# LED_Matrix-2.net
KiCad netlist of a schematic drawn in Altium Designer
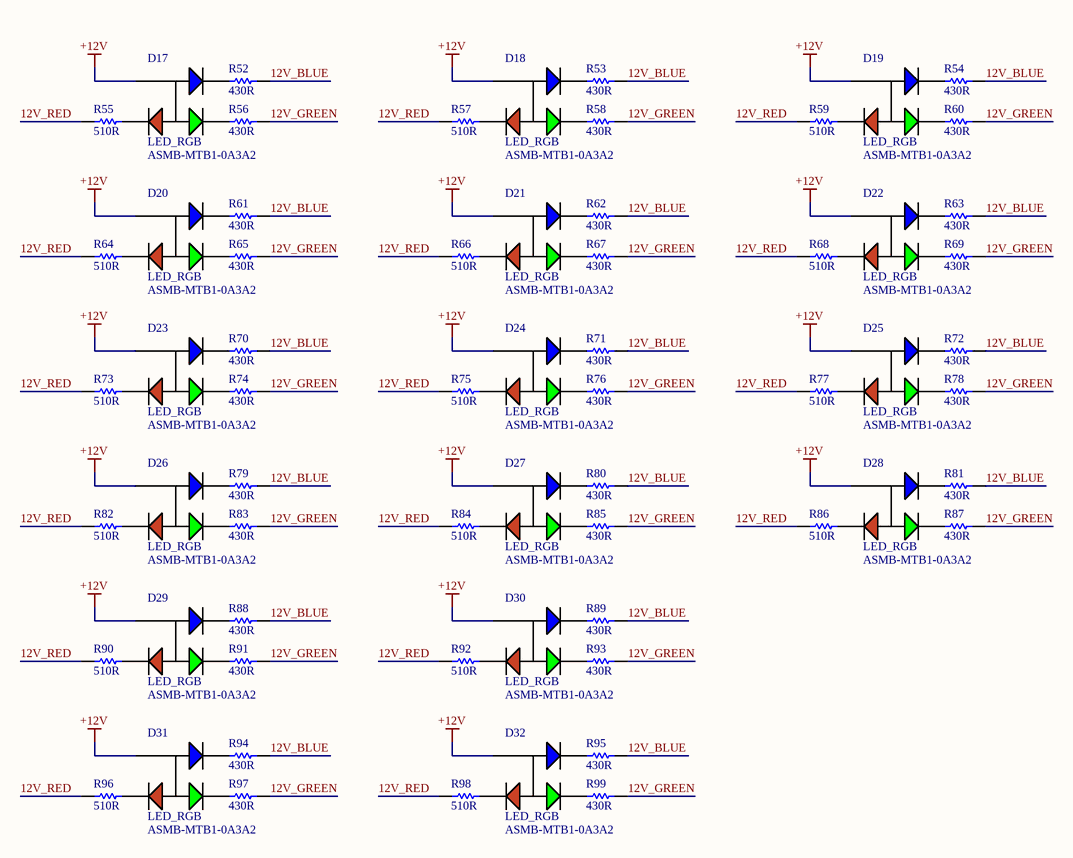
[diagram p0: LED Matrix-2.SchDoc]

(export (version "E")
  (design (tool "Eeschema 10.0.6"))
  (components
    (comp (ref "D17")
      (value "LED_RGB")
      (footprint "LED_RGB")
      (description "LED RGB DIFFUSED 4PLCC SMD")
      (fields (field (name "MANUFACTURER PART NUMBER 1") "ASMB-MTB1-0A3A2"))
      (libsource (lib "UWRT_Schematic_Library_2020") (part "LED_RGB"))
    )
    (comp (ref "D18")
      (value "LED_RGB")
      (footprint "LED_RGB")
      (description "LED RGB DIFFUSED 4PLCC SMD")
      (fields (field (name "MANUFACTURER PART NUMBER 1") "ASMB-MTB1-0A3A2"))
      (libsource (lib "UWRT_Schematic_Library_2020") (part "LED_RGB"))
    )
    (comp (ref "D19")
      (value "LED_RGB")
      (footprint "LED_RGB")
      (description "LED RGB DIFFUSED 4PLCC SMD")
      (fields (field (name "MANUFACTURER PART NUMBER 1") "ASMB-MTB1-0A3A2"))
      (libsource (lib "UWRT_Schematic_Library_2020") (part "LED_RGB"))
    )
    (comp (ref "D20")
      (value "LED_RGB")
      (footprint "LED_RGB")
      (description "LED RGB DIFFUSED 4PLCC SMD")
      (fields (field (name "MANUFACTURER PART NUMBER 1") "ASMB-MTB1-0A3A2"))
      (libsource (lib "UWRT_Schematic_Library_2020") (part "LED_RGB"))
    )
    (comp (ref "D21")
      (value "LED_RGB")
      (footprint "LED_RGB")
      (description "LED RGB DIFFUSED 4PLCC SMD")
      (fields (field (name "MANUFACTURER PART NUMBER 1") "ASMB-MTB1-0A3A2"))
      (libsource (lib "UWRT_Schematic_Library_2020") (part "LED_RGB"))
    )
    (comp (ref "D22")
      (value "LED_RGB")
      (footprint "LED_RGB")
      (description "LED RGB DIFFUSED 4PLCC SMD")
      (fields (field (name "MANUFACTURER PART NUMBER 1") "ASMB-MTB1-0A3A2"))
      (libsource (lib "UWRT_Schematic_Library_2020") (part "LED_RGB"))
    )
    (comp (ref "D23")
      (value "LED_RGB")
      (footprint "LED_RGB")
      (description "LED RGB DIFFUSED 4PLCC SMD")
      (fields (field (name "MANUFACTURER PART NUMBER 1") "ASMB-MTB1-0A3A2"))
      (libsource (lib "UWRT_Schematic_Library_2020") (part "LED_RGB"))
    )
    (comp (ref "D24")
      (value "LED_RGB")
      (footprint "LED_RGB")
      (description "LED RGB DIFFUSED 4PLCC SMD")
      (fields (field (name "MANUFACTURER PART NUMBER 1") "ASMB-MTB1-0A3A2"))
      (libsource (lib "UWRT_Schematic_Library_2020") (part "LED_RGB"))
    )
    (comp (ref "D25")
      (value "LED_RGB")
      (footprint "LED_RGB")
      (description "LED RGB DIFFUSED 4PLCC SMD")
      (fields (field (name "MANUFACTURER PART NUMBER 1") "ASMB-MTB1-0A3A2"))
      (libsource (lib "UWRT_Schematic_Library_2020") (part "LED_RGB"))
    )
    (comp (ref "D26")
      (value "LED_RGB")
      (footprint "LED_RGB")
      (description "LED RGB DIFFUSED 4PLCC SMD")
      (fields (field (name "MANUFACTURER PART NUMBER 1") "ASMB-MTB1-0A3A2"))
      (libsource (lib "UWRT_Schematic_Library_2020") (part "LED_RGB"))
    )
    (comp (ref "D27")
      (value "LED_RGB")
      (footprint "LED_RGB")
      (description "LED RGB DIFFUSED 4PLCC SMD")
      (fields (field (name "MANUFACTURER PART NUMBER 1") "ASMB-MTB1-0A3A2"))
      (libsource (lib "UWRT_Schematic_Library_2020") (part "LED_RGB"))
    )
    (comp (ref "D28")
      (value "LED_RGB")
      (footprint "LED_RGB")
      (description "LED RGB DIFFUSED 4PLCC SMD")
      (fields (field (name "MANUFACTURER PART NUMBER 1") "ASMB-MTB1-0A3A2"))
      (libsource (lib "UWRT_Schematic_Library_2020") (part "LED_RGB"))
    )
    (comp (ref "D29")
      (value "LED_RGB")
      (footprint "LED_RGB")
      (description "LED RGB DIFFUSED 4PLCC SMD")
      (fields (field (name "MANUFACTURER PART NUMBER 1") "ASMB-MTB1-0A3A2"))
      (libsource (lib "UWRT_Schematic_Library_2020") (part "LED_RGB"))
    )
    (comp (ref "D30")
      (value "LED_RGB")
      (footprint "LED_RGB")
      (description "LED RGB DIFFUSED 4PLCC SMD")
      (fields (field (name "MANUFACTURER PART NUMBER 1") "ASMB-MTB1-0A3A2"))
      (libsource (lib "UWRT_Schematic_Library_2020") (part "LED_RGB"))
    )
    (comp (ref "D31")
      (value "LED_RGB")
      (footprint "LED_RGB")
      (description "LED RGB DIFFUSED 4PLCC SMD")
      (fields (field (name "MANUFACTURER PART NUMBER 1") "ASMB-MTB1-0A3A2"))
      (libsource (lib "UWRT_Schematic_Library_2020") (part "LED_RGB"))
    )
    (comp (ref "D32")
      (value "LED_RGB")
      (footprint "LED_RGB")
      (description "LED RGB DIFFUSED 4PLCC SMD")
      (fields (field (name "MANUFACTURER PART NUMBER 1") "ASMB-MTB1-0A3A2"))
      (libsource (lib "UWRT_Schematic_Library_2020") (part "LED_RGB"))
    )
    (comp (ref "R52")
      (value "430R")
      (footprint "RESC2012X60N")
      (description "RES SMD 430 OHM 1% 1/8W 0805")
      (fields (field (name "TOLERANCE") "1%") (field (name "Comment") "RES_430R_0805"))
      (libsource (lib "UWRT_Schematic_Library_2020") (part "RES_430R_0805"))
    )
    (comp (ref "R53")
      (value "430R")
      (footprint "RESC2012X60N")
      (description "RES SMD 430 OHM 1% 1/8W 0805")
      (fields (field (name "TOLERANCE") "1%") (field (name "Comment") "RES_430R_0805"))
      (libsource (lib "UWRT_Schematic_Library_2020") (part "RES_430R_0805"))
    )
    (comp (ref "R54")
      (value "430R")
      (footprint "RESC2012X60N")
      (description "RES SMD 430 OHM 1% 1/8W 0805")
      (fields (field (name "TOLERANCE") "1%") (field (name "Comment") "RES_430R_0805"))
      (libsource (lib "UWRT_Schematic_Library_2020") (part "RES_430R_0805"))
    )
    (comp (ref "R55")
      (value "510R")
      (footprint "RESC2012X60N")
      (description "RES SMD 510 OHM 1% 1/8W 0805")
      (fields (field (name "TOLERANCE") "1%") (field (name "Comment") "RES_510R_0805"))
      (libsource (lib "UWRT_Schematic_Library_2020") (part "RES_510R_0805"))
    )
    (comp (ref "R56")
      (value "430R")
      (footprint "RESC2012X60N")
      (description "RES SMD 430 OHM 1% 1/8W 0805")
      (fields (field (name "TOLERANCE") "1%") (field (name "Comment") "RES_430R_0805"))
      (libsource (lib "UWRT_Schematic_Library_2020") (part "RES_430R_0805"))
    )
    (comp (ref "R57")
      (value "510R")
      (footprint "RESC2012X60N")
      (description "RES SMD 510 OHM 1% 1/8W 0805")
      (fields (field (name "TOLERANCE") "1%") (field (name "Comment") "RES_510R_0805"))
      (libsource (lib "UWRT_Schematic_Library_2020") (part "RES_510R_0805"))
    )
    (comp (ref "R58")
      (value "430R")
      (footprint "RESC2012X60N")
      (description "RES SMD 430 OHM 1% 1/8W 0805")
      (fields (field (name "TOLERANCE") "1%") (field (name "Comment") "RES_430R_0805"))
      (libsource (lib "UWRT_Schematic_Library_2020") (part "RES_430R_0805"))
    )
    (comp (ref "R59")
      (value "510R")
      (footprint "RESC2012X60N")
      (description "RES SMD 510 OHM 1% 1/8W 0805")
      (fields (field (name "TOLERANCE") "1%") (field (name "Comment") "RES_510R_0805"))
      (libsource (lib "UWRT_Schematic_Library_2020") (part "RES_510R_0805"))
    )
    (comp (ref "R60")
      (value "430R")
      (footprint "RESC2012X60N")
      (description "RES SMD 430 OHM 1% 1/8W 0805")
      (fields (field (name "TOLERANCE") "1%") (field (name "Comment") "RES_430R_0805"))
      (libsource (lib "UWRT_Schematic_Library_2020") (part "RES_430R_0805"))
    )
    (comp (ref "R61")
      (value "430R")
      (footprint "RESC2012X60N")
      (description "RES SMD 430 OHM 1% 1/8W 0805")
      (fields (field (name "TOLERANCE") "1%") (field (name "Comment") "RES_430R_0805"))
      (libsource (lib "UWRT_Schematic_Library_2020") (part "RES_430R_0805"))
    )
    (comp (ref "R62")
      (value "430R")
      (footprint "RESC2012X60N")
      (description "RES SMD 430 OHM 1% 1/8W 0805")
      (fields (field (name "TOLERANCE") "1%") (field (name "Comment") "RES_430R_0805"))
      (libsource (lib "UWRT_Schematic_Library_2020") (part "RES_430R_0805"))
    )
    (comp (ref "R63")
      (value "430R")
      (footprint "RESC2012X60N")
      (description "RES SMD 430 OHM 1% 1/8W 0805")
      (fields (field (name "TOLERANCE") "1%") (field (name "Comment") "RES_430R_0805"))
      (libsource (lib "UWRT_Schematic_Library_2020") (part "RES_430R_0805"))
    )
    (comp (ref "R64")
      (value "510R")
      (footprint "RESC2012X60N")
      (description "RES SMD 510 OHM 1% 1/8W 0805")
      (fields (field (name "TOLERANCE") "1%") (field (name "Comment") "RES_510R_0805"))
      (libsource (lib "UWRT_Schematic_Library_2020") (part "RES_510R_0805"))
    )
    (comp (ref "R65")
      (value "430R")
      (footprint "RESC2012X60N")
      (description "RES SMD 430 OHM 1% 1/8W 0805")
      (fields (field (name "TOLERANCE") "1%") (field (name "Comment") "RES_430R_0805"))
      (libsource (lib "UWRT_Schematic_Library_2020") (part "RES_430R_0805"))
    )
    (comp (ref "R66")
      (value "510R")
      (footprint "RESC2012X60N")
      (description "RES SMD 510 OHM 1% 1/8W 0805")
      (fields (field (name "TOLERANCE") "1%") (field (name "Comment") "RES_510R_0805"))
      (libsource (lib "UWRT_Schematic_Library_2020") (part "RES_510R_0805"))
    )
    (comp (ref "R67")
      (value "430R")
      (footprint "RESC2012X60N")
      (description "RES SMD 430 OHM 1% 1/8W 0805")
      (fields (field (name "TOLERANCE") "1%") (field (name "Comment") "RES_430R_0805"))
      (libsource (lib "UWRT_Schematic_Library_2020") (part "RES_430R_0805"))
    )
    (comp (ref "R68")
      (value "510R")
      (footprint "RESC2012X60N")
      (description "RES SMD 510 OHM 1% 1/8W 0805")
      (fields (field (name "TOLERANCE") "1%") (field (name "Comment") "RES_510R_0805"))
      (libsource (lib "UWRT_Schematic_Library_2020") (part "RES_510R_0805"))
    )
    (comp (ref "R69")
      (value "430R")
      (footprint "RESC2012X60N")
      (description "RES SMD 430 OHM 1% 1/8W 0805")
      (fields (field (name "TOLERANCE") "1%") (field (name "Comment") "RES_430R_0805"))
      (libsource (lib "UWRT_Schematic_Library_2020") (part "RES_430R_0805"))
    )
    (comp (ref "R70")
      (value "430R")
      (footprint "RESC2012X60N")
      (description "RES SMD 430 OHM 1% 1/8W 0805")
      (fields (field (name "TOLERANCE") "1%") (field (name "Comment") "RES_430R_0805"))
      (libsource (lib "UWRT_Schematic_Library_2020") (part "RES_430R_0805"))
    )
    (comp (ref "R71")
      (value "430R")
      (footprint "RESC2012X60N")
      (description "RES SMD 430 OHM 1% 1/8W 0805")
      (fields (field (name "TOLERANCE") "1%") (field (name "Comment") "RES_430R_0805"))
      (libsource (lib "UWRT_Schematic_Library_2020") (part "RES_430R_0805"))
    )
    (comp (ref "R72")
      (value "430R")
      (footprint "RESC2012X60N")
      (description "RES SMD 430 OHM 1% 1/8W 0805")
      (fields (field (name "TOLERANCE") "1%") (field (name "Comment") "RES_430R_0805"))
      (libsource (lib "UWRT_Schematic_Library_2020") (part "RES_430R_0805"))
    )
    (comp (ref "R73")
      (value "510R")
      (footprint "RESC2012X60N")
      (description "RES SMD 510 OHM 1% 1/8W 0805")
      (fields (field (name "TOLERANCE") "1%") (field (name "Comment") "RES_510R_0805"))
      (libsource (lib "UWRT_Schematic_Library_2020") (part "RES_510R_0805"))
    )
    (comp (ref "R74")
      (value "430R")
      (footprint "RESC2012X60N")
      (description "RES SMD 430 OHM 1% 1/8W 0805")
      (fields (field (name "TOLERANCE") "1%") (field (name "Comment") "RES_430R_0805"))
      (libsource (lib "UWRT_Schematic_Library_2020") (part "RES_430R_0805"))
    )
    (comp (ref "R75")
      (value "510R")
      (footprint "RESC2012X60N")
      (description "RES SMD 510 OHM 1% 1/8W 0805")
      (fields (field (name "TOLERANCE") "1%") (field (name "Comment") "RES_510R_0805"))
      (libsource (lib "UWRT_Schematic_Library_2020") (part "RES_510R_0805"))
    )
    (comp (ref "R76")
      (value "430R")
      (footprint "RESC2012X60N")
      (description "RES SMD 430 OHM 1% 1/8W 0805")
      (fields (field (name "TOLERANCE") "1%") (field (name "Comment") "RES_430R_0805"))
      (libsource (lib "UWRT_Schematic_Library_2020") (part "RES_430R_0805"))
    )
    (comp (ref "R77")
      (value "510R")
      (footprint "RESC2012X60N")
      (description "RES SMD 510 OHM 1% 1/8W 0805")
      (fields (field (name "TOLERANCE") "1%") (field (name "Comment") "RES_510R_0805"))
      (libsource (lib "UWRT_Schematic_Library_2020") (part "RES_510R_0805"))
    )
    (comp (ref "R78")
      (value "430R")
      (footprint "RESC2012X60N")
      (description "RES SMD 430 OHM 1% 1/8W 0805")
      (fields (field (name "TOLERANCE") "1%") (field (name "Comment") "RES_430R_0805"))
      (libsource (lib "UWRT_Schematic_Library_2020") (part "RES_430R_0805"))
    )
    (comp (ref "R79")
      (value "430R")
      (footprint "RESC2012X60N")
      (description "RES SMD 430 OHM 1% 1/8W 0805")
      (fields (field (name "TOLERANCE") "1%") (field (name "Comment") "RES_430R_0805"))
      (libsource (lib "UWRT_Schematic_Library_2020") (part "RES_430R_0805"))
    )
    (comp (ref "R80")
      (value "430R")
      (footprint "RESC2012X60N")
      (description "RES SMD 430 OHM 1% 1/8W 0805")
      (fields (field (name "TOLERANCE") "1%") (field (name "Comment") "RES_430R_0805"))
      (libsource (lib "UWRT_Schematic_Library_2020") (part "RES_430R_0805"))
    )
    (comp (ref "R81")
      (value "430R")
      (footprint "RESC2012X60N")
      (description "RES SMD 430 OHM 1% 1/8W 0805")
      (fields (field (name "TOLERANCE") "1%") (field (name "Comment") "RES_430R_0805"))
      (libsource (lib "UWRT_Schematic_Library_2020") (part "RES_430R_0805"))
    )
    (comp (ref "R82")
      (value "510R")
      (footprint "RESC2012X60N")
      (description "RES SMD 510 OHM 1% 1/8W 0805")
      (fields (field (name "TOLERANCE") "1%") (field (name "Comment") "RES_510R_0805"))
      (libsource (lib "UWRT_Schematic_Library_2020") (part "RES_510R_0805"))
    )
    (comp (ref "R83")
      (value "430R")
      (footprint "RESC2012X60N")
      (description "RES SMD 430 OHM 1% 1/8W 0805")
      (fields (field (name "TOLERANCE") "1%") (field (name "Comment") "RES_430R_0805"))
      (libsource (lib "UWRT_Schematic_Library_2020") (part "RES_430R_0805"))
    )
    (comp (ref "R84")
      (value "510R")
      (footprint "RESC2012X60N")
      (description "RES SMD 510 OHM 1% 1/8W 0805")
      (fields (field (name "TOLERANCE") "1%") (field (name "Comment") "RES_510R_0805"))
      (libsource (lib "UWRT_Schematic_Library_2020") (part "RES_510R_0805"))
    )
    (comp (ref "R85")
      (value "430R")
      (footprint "RESC2012X60N")
      (description "RES SMD 430 OHM 1% 1/8W 0805")
      (fields (field (name "TOLERANCE") "1%") (field (name "Comment") "RES_430R_0805"))
      (libsource (lib "UWRT_Schematic_Library_2020") (part "RES_430R_0805"))
    )
    (comp (ref "R86")
      (value "510R")
      (footprint "RESC2012X60N")
      (description "RES SMD 510 OHM 1% 1/8W 0805")
      (fields (field (name "TOLERANCE") "1%") (field (name "Comment") "RES_510R_0805"))
      (libsource (lib "UWRT_Schematic_Library_2020") (part "RES_510R_0805"))
    )
    (comp (ref "R87")
      (value "430R")
      (footprint "RESC2012X60N")
      (description "RES SMD 430 OHM 1% 1/8W 0805")
      (fields (field (name "TOLERANCE") "1%") (field (name "Comment") "RES_430R_0805"))
      (libsource (lib "UWRT_Schematic_Library_2020") (part "RES_430R_0805"))
    )
    (comp (ref "R88")
      (value "430R")
      (footprint "RESC2012X60N")
      (description "RES SMD 430 OHM 1% 1/8W 0805")
      (fields (field (name "TOLERANCE") "1%") (field (name "Comment") "RES_430R_0805"))
      (libsource (lib "UWRT_Schematic_Library_2020") (part "RES_430R_0805"))
    )
    (comp (ref "R89")
      (value "430R")
      (footprint "RESC2012X60N")
      (description "RES SMD 430 OHM 1% 1/8W 0805")
      (fields (field (name "TOLERANCE") "1%") (field (name "Comment") "RES_430R_0805"))
      (libsource (lib "UWRT_Schematic_Library_2020") (part "RES_430R_0805"))
    )
    (comp (ref "R90")
      (value "510R")
      (footprint "RESC2012X60N")
      (description "RES SMD 510 OHM 1% 1/8W 0805")
      (fields (field (name "TOLERANCE") "1%") (field (name "Comment") "RES_510R_0805"))
      (libsource (lib "UWRT_Schematic_Library_2020") (part "RES_510R_0805"))
    )
    (comp (ref "R91")
      (value "430R")
      (footprint "RESC2012X60N")
      (description "RES SMD 430 OHM 1% 1/8W 0805")
      (fields (field (name "TOLERANCE") "1%") (field (name "Comment") "RES_430R_0805"))
      (libsource (lib "UWRT_Schematic_Library_2020") (part "RES_430R_0805"))
    )
    (comp (ref "R92")
      (value "510R")
      (footprint "RESC2012X60N")
      (description "RES SMD 510 OHM 1% 1/8W 0805")
      (fields (field (name "TOLERANCE") "1%") (field (name "Comment") "RES_510R_0805"))
      (libsource (lib "UWRT_Schematic_Library_2020") (part "RES_510R_0805"))
    )
    (comp (ref "R93")
      (value "430R")
      (footprint "RESC2012X60N")
      (description "RES SMD 430 OHM 1% 1/8W 0805")
      (fields (field (name "TOLERANCE") "1%") (field (name "Comment") "RES_430R_0805"))
      (libsource (lib "UWRT_Schematic_Library_2020") (part "RES_430R_0805"))
    )
    (comp (ref "R94")
      (value "430R")
      (footprint "RESC2012X60N")
      (description "RES SMD 430 OHM 1% 1/8W 0805")
      (fields (field (name "TOLERANCE") "1%") (field (name "Comment") "RES_430R_0805"))
      (libsource (lib "UWRT_Schematic_Library_2020") (part "RES_430R_0805"))
    )
    (comp (ref "R95")
      (value "430R")
      (footprint "RESC2012X60N")
      (description "RES SMD 430 OHM 1% 1/8W 0805")
      (fields (field (name "TOLERANCE") "1%") (field (name "Comment") "RES_430R_0805"))
      (libsource (lib "UWRT_Schematic_Library_2020") (part "RES_430R_0805"))
    )
    (comp (ref "R96")
      (value "510R")
      (footprint "RESC2012X60N")
      (description "RES SMD 510 OHM 1% 1/8W 0805")
      (fields (field (name "TOLERANCE") "1%") (field (name "Comment") "RES_510R_0805"))
      (libsource (lib "UWRT_Schematic_Library_2020") (part "RES_510R_0805"))
    )
    (comp (ref "R97")
      (value "430R")
      (footprint "RESC2012X60N")
      (description "RES SMD 430 OHM 1% 1/8W 0805")
      (fields (field (name "TOLERANCE") "1%") (field (name "Comment") "RES_430R_0805"))
      (libsource (lib "UWRT_Schematic_Library_2020") (part "RES_430R_0805"))
    )
    (comp (ref "R98")
      (value "510R")
      (footprint "RESC2012X60N")
      (description "RES SMD 510 OHM 1% 1/8W 0805")
      (fields (field (name "TOLERANCE") "1%") (field (name "Comment") "RES_510R_0805"))
      (libsource (lib "UWRT_Schematic_Library_2020") (part "RES_510R_0805"))
    )
    (comp (ref "R99")
      (value "430R")
      (footprint "RESC2012X60N")
      (description "RES SMD 430 OHM 1% 1/8W 0805")
      (fields (field (name "TOLERANCE") "1%") (field (name "Comment") "RES_430R_0805"))
      (libsource (lib "UWRT_Schematic_Library_2020") (part "RES_430R_0805"))
    )
  )
  (nets
    (net (code "1") (name "+12V") (class "Default")
      (node (ref "D17") (pin "4") (pinfunction "9_4") (pintype "passive"))
      (node (ref "D18") (pin "4") (pinfunction "9_4") (pintype "passive"))
      (node (ref "D19") (pin "4") (pinfunction "9_4") (pintype "passive"))
      (node (ref "D20") (pin "4") (pinfunction "9_4") (pintype "passive"))
      (node (ref "D21") (pin "4") (pinfunction "9_4") (pintype "passive"))
      (node (ref "D22") (pin "4") (pinfunction "9_4") (pintype "passive"))
      (node (ref "D23") (pin "4") (pinfunction "9_4") (pintype "passive"))
      (node (ref "D24") (pin "4") (pinfunction "9_4") (pintype "passive"))
      (node (ref "D25") (pin "4") (pinfunction "9_4") (pintype "passive"))
      (node (ref "D26") (pin "4") (pinfunction "9_4") (pintype "passive"))
      (node (ref "D27") (pin "4") (pinfunction "9_4") (pintype "passive"))
      (node (ref "D28") (pin "4") (pinfunction "9_4") (pintype "passive"))
      (node (ref "D29") (pin "4") (pinfunction "9_4") (pintype "passive"))
      (node (ref "D30") (pin "4") (pinfunction "9_4") (pintype "passive"))
      (node (ref "D31") (pin "4") (pinfunction "9_4") (pintype "passive"))
      (node (ref "D32") (pin "4") (pinfunction "9_4") (pintype "passive"))
    )
    (net (code "2") (name "/12V_BLUE") (class "Default")
      (node (ref "R52") (pin "1") (pinfunction "1_1") (pintype "passive"))
      (node (ref "R53") (pin "1") (pinfunction "1_1") (pintype "passive"))
      (node (ref "R54") (pin "1") (pinfunction "1_1") (pintype "passive"))
      (node (ref "R61") (pin "1") (pinfunction "1_1") (pintype "passive"))
      (node (ref "R62") (pin "1") (pinfunction "1_1") (pintype "passive"))
      (node (ref "R63") (pin "1") (pinfunction "1_1") (pintype "passive"))
      (node (ref "R70") (pin "1") (pinfunction "1_1") (pintype "passive"))
      (node (ref "R71") (pin "1") (pinfunction "1_1") (pintype "passive"))
      (node (ref "R72") (pin "1") (pinfunction "1_1") (pintype "passive"))
      (node (ref "R79") (pin "1") (pinfunction "1_1") (pintype "passive"))
      (node (ref "R80") (pin "1") (pinfunction "1_1") (pintype "passive"))
      (node (ref "R81") (pin "1") (pinfunction "1_1") (pintype "passive"))
      (node (ref "R88") (pin "1") (pinfunction "1_1") (pintype "passive"))
      (node (ref "R89") (pin "1") (pinfunction "1_1") (pintype "passive"))
      (node (ref "R94") (pin "1") (pinfunction "1_1") (pintype "passive"))
      (node (ref "R95") (pin "1") (pinfunction "1_1") (pintype "passive"))
    )
    (net (code "3") (name "/12V_GREEN") (class "Default")
      (node (ref "R56") (pin "1") (pinfunction "1_1") (pintype "passive"))
      (node (ref "R58") (pin "1") (pinfunction "1_1") (pintype "passive"))
      (node (ref "R60") (pin "1") (pinfunction "1_1") (pintype "passive"))
      (node (ref "R65") (pin "1") (pinfunction "1_1") (pintype "passive"))
      (node (ref "R67") (pin "1") (pinfunction "1_1") (pintype "passive"))
      (node (ref "R69") (pin "1") (pinfunction "1_1") (pintype "passive"))
      (node (ref "R74") (pin "1") (pinfunction "1_1") (pintype "passive"))
      (node (ref "R76") (pin "1") (pinfunction "1_1") (pintype "passive"))
      (node (ref "R78") (pin "1") (pinfunction "1_1") (pintype "passive"))
      (node (ref "R83") (pin "1") (pinfunction "1_1") (pintype "passive"))
      (node (ref "R85") (pin "1") (pinfunction "1_1") (pintype "passive"))
      (node (ref "R87") (pin "1") (pinfunction "1_1") (pintype "passive"))
      (node (ref "R91") (pin "1") (pinfunction "1_1") (pintype "passive"))
      (node (ref "R93") (pin "1") (pinfunction "1_1") (pintype "passive"))
      (node (ref "R97") (pin "1") (pinfunction "1_1") (pintype "passive"))
      (node (ref "R99") (pin "1") (pinfunction "1_1") (pintype "passive"))
    )
    (net (code "4") (name "/12V_RED") (class "Default")
      (node (ref "R55") (pin "2") (pinfunction "2_2") (pintype "passive"))
      (node (ref "R57") (pin "2") (pinfunction "2_2") (pintype "passive"))
      (node (ref "R59") (pin "2") (pinfunction "2_2") (pintype "passive"))
      (node (ref "R64") (pin "2") (pinfunction "2_2") (pintype "passive"))
      (node (ref "R66") (pin "2") (pinfunction "2_2") (pintype "passive"))
      (node (ref "R68") (pin "2") (pinfunction "2_2") (pintype "passive"))
      (node (ref "R73") (pin "2") (pinfunction "2_2") (pintype "passive"))
      (node (ref "R75") (pin "2") (pinfunction "2_2") (pintype "passive"))
      (node (ref "R77") (pin "2") (pinfunction "2_2") (pintype "passive"))
      (node (ref "R82") (pin "2") (pinfunction "2_2") (pintype "passive"))
      (node (ref "R84") (pin "2") (pinfunction "2_2") (pintype "passive"))
      (node (ref "R86") (pin "2") (pinfunction "2_2") (pintype "passive"))
      (node (ref "R90") (pin "2") (pinfunction "2_2") (pintype "passive"))
      (node (ref "R92") (pin "2") (pinfunction "2_2") (pintype "passive"))
      (node (ref "R96") (pin "2") (pinfunction "2_2") (pintype "passive"))
      (node (ref "R98") (pin "2") (pinfunction "2_2") (pintype "passive"))
    )
    (net (code "5") (name "Net-(D17-10)") (class "Default")
      (node (ref "D17") (pin "3") (pinfunction "10_3") (pintype "passive"))
      (node (ref "R52") (pin "2") (pinfunction "2_2") (pintype "passive"))
    )
    (net (code "6") (name "Net-(D17-11)") (class "Default")
      (node (ref "D17") (pin "1") (pinfunction "11_1") (pintype "passive"))
      (node (ref "R55") (pin "1") (pinfunction "1_1") (pintype "passive"))
    )
    (net (code "7") (name "Net-(D17-12)") (class "Default")
      (node (ref "D17") (pin "2") (pinfunction "12_2") (pintype "passive"))
      (node (ref "R56") (pin "2") (pinfunction "2_2") (pintype "passive"))
    )
    (net (code "8") (name "Net-(D18-10)") (class "Default")
      (node (ref "D18") (pin "3") (pinfunction "10_3") (pintype "passive"))
      (node (ref "R53") (pin "2") (pinfunction "2_2") (pintype "passive"))
    )
    (net (code "9") (name "Net-(D18-11)") (class "Default")
      (node (ref "D18") (pin "1") (pinfunction "11_1") (pintype "passive"))
      (node (ref "R57") (pin "1") (pinfunction "1_1") (pintype "passive"))
    )
    (net (code "10") (name "Net-(D18-12)") (class "Default")
      (node (ref "D18") (pin "2") (pinfunction "12_2") (pintype "passive"))
      (node (ref "R58") (pin "2") (pinfunction "2_2") (pintype "passive"))
    )
    (net (code "11") (name "Net-(D19-10)") (class "Default")
      (node (ref "D19") (pin "3") (pinfunction "10_3") (pintype "passive"))
      (node (ref "R54") (pin "2") (pinfunction "2_2") (pintype "passive"))
    )
    (net (code "12") (name "Net-(D19-11)") (class "Default")
      (node (ref "D19") (pin "1") (pinfunction "11_1") (pintype "passive"))
      (node (ref "R59") (pin "1") (pinfunction "1_1") (pintype "passive"))
    )
    (net (code "13") (name "Net-(D19-12)") (class "Default")
      (node (ref "D19") (pin "2") (pinfunction "12_2") (pintype "passive"))
      (node (ref "R60") (pin "2") (pinfunction "2_2") (pintype "passive"))
    )
    (net (code "14") (name "Net-(D20-10)") (class "Default")
      (node (ref "D20") (pin "3") (pinfunction "10_3") (pintype "passive"))
      (node (ref "R61") (pin "2") (pinfunction "2_2") (pintype "passive"))
    )
    (net (code "15") (name "Net-(D20-11)") (class "Default")
      (node (ref "D20") (pin "1") (pinfunction "11_1") (pintype "passive"))
      (node (ref "R64") (pin "1") (pinfunction "1_1") (pintype "passive"))
    )
    (net (code "16") (name "Net-(D20-12)") (class "Default")
      (node (ref "D20") (pin "2") (pinfunction "12_2") (pintype "passive"))
      (node (ref "R65") (pin "2") (pinfunction "2_2") (pintype "passive"))
    )
    (net (code "17") (name "Net-(D21-10)") (class "Default")
      (node (ref "D21") (pin "3") (pinfunction "10_3") (pintype "passive"))
      (node (ref "R62") (pin "2") (pinfunction "2_2") (pintype "passive"))
    )
    (net (code "18") (name "Net-(D21-11)") (class "Default")
      (node (ref "D21") (pin "1") (pinfunction "11_1") (pintype "passive"))
      (node (ref "R66") (pin "1") (pinfunction "1_1") (pintype "passive"))
    )
    (net (code "19") (name "Net-(D21-12)") (class "Default")
      (node (ref "D21") (pin "2") (pinfunction "12_2") (pintype "passive"))
      (node (ref "R67") (pin "2") (pinfunction "2_2") (pintype "passive"))
    )
    (net (code "20") (name "Net-(D22-10)") (class "Default")
      (node (ref "D22") (pin "3") (pinfunction "10_3") (pintype "passive"))
      (node (ref "R63") (pin "2") (pinfunction "2_2") (pintype "passive"))
    )
    (net (code "21") (name "Net-(D22-11)") (class "Default")
      (node (ref "D22") (pin "1") (pinfunction "11_1") (pintype "passive"))
      (node (ref "R68") (pin "1") (pinfunction "1_1") (pintype "passive"))
    )
    (net (code "22") (name "Net-(D22-12)") (class "Default")
      (node (ref "D22") (pin "2") (pinfunction "12_2") (pintype "passive"))
      (node (ref "R69") (pin "2") (pinfunction "2_2") (pintype "passive"))
    )
    (net (code "23") (name "Net-(D23-10)") (class "Default")
      (node (ref "D23") (pin "3") (pinfunction "10_3") (pintype "passive"))
      (node (ref "R70") (pin "2") (pinfunction "2_2") (pintype "passive"))
    )
    (net (code "24") (name "Net-(D23-11)") (class "Default")
      (node (ref "D23") (pin "1") (pinfunction "11_1") (pintype "passive"))
      (node (ref "R73") (pin "1") (pinfunction "1_1") (pintype "passive"))
    )
    (net (code "25") (name "Net-(D23-12)") (class "Default")
      (node (ref "D23") (pin "2") (pinfunction "12_2") (pintype "passive"))
      (node (ref "R74") (pin "2") (pinfunction "2_2") (pintype "passive"))
    )
    (net (code "26") (name "Net-(D24-10)") (class "Default")
      (node (ref "D24") (pin "3") (pinfunction "10_3") (pintype "passive"))
      (node (ref "R71") (pin "2") (pinfunction "2_2") (pintype "passive"))
    )
    (net (code "27") (name "Net-(D24-11)") (class "Default")
      (node (ref "D24") (pin "1") (pinfunction "11_1") (pintype "passive"))
      (node (ref "R75") (pin "1") (pinfunction "1_1") (pintype "passive"))
    )
    (net (code "28") (name "Net-(D24-12)") (class "Default")
      (node (ref "D24") (pin "2") (pinfunction "12_2") (pintype "passive"))
      (node (ref "R76") (pin "2") (pinfunction "2_2") (pintype "passive"))
    )
    (net (code "29") (name "Net-(D25-10)") (class "Default")
      (node (ref "D25") (pin "3") (pinfunction "10_3") (pintype "passive"))
      (node (ref "R72") (pin "2") (pinfunction "2_2") (pintype "passive"))
    )
    (net (code "30") (name "Net-(D25-11)") (class "Default")
      (node (ref "D25") (pin "1") (pinfunction "11_1") (pintype "passive"))
      (node (ref "R77") (pin "1") (pinfunction "1_1") (pintype "passive"))
    )
    (net (code "31") (name "Net-(D25-12)") (class "Default")
      (node (ref "D25") (pin "2") (pinfunction "12_2") (pintype "passive"))
      (node (ref "R78") (pin "2") (pinfunction "2_2") (pintype "passive"))
    )
    (net (code "32") (name "Net-(D26-10)") (class "Default")
      (node (ref "D26") (pin "3") (pinfunction "10_3") (pintype "passive"))
      (node (ref "R79") (pin "2") (pinfunction "2_2") (pintype "passive"))
    )
    (net (code "33") (name "Net-(D26-11)") (class "Default")
      (node (ref "D26") (pin "1") (pinfunction "11_1") (pintype "passive"))
      (node (ref "R82") (pin "1") (pinfunction "1_1") (pintype "passive"))
    )
    (net (code "34") (name "Net-(D26-12)") (class "Default")
      (node (ref "D26") (pin "2") (pinfunction "12_2") (pintype "passive"))
      (node (ref "R83") (pin "2") (pinfunction "2_2") (pintype "passive"))
    )
    (net (code "35") (name "Net-(D27-10)") (class "Default")
      (node (ref "D27") (pin "3") (pinfunction "10_3") (pintype "passive"))
      (node (ref "R80") (pin "2") (pinfunction "2_2") (pintype "passive"))
    )
    (net (code "36") (name "Net-(D27-11)") (class "Default")
      (node (ref "D27") (pin "1") (pinfunction "11_1") (pintype "passive"))
      (node (ref "R84") (pin "1") (pinfunction "1_1") (pintype "passive"))
    )
    (net (code "37") (name "Net-(D27-12)") (class "Default")
      (node (ref "D27") (pin "2") (pinfunction "12_2") (pintype "passive"))
      (node (ref "R85") (pin "2") (pinfunction "2_2") (pintype "passive"))
    )
    (net (code "38") (name "Net-(D28-10)") (class "Default")
      (node (ref "D28") (pin "3") (pinfunction "10_3") (pintype "passive"))
      (node (ref "R81") (pin "2") (pinfunction "2_2") (pintype "passive"))
    )
    (net (code "39") (name "Net-(D28-11)") (class "Default")
      (node (ref "D28") (pin "1") (pinfunction "11_1") (pintype "passive"))
      (node (ref "R86") (pin "1") (pinfunction "1_1") (pintype "passive"))
    )
    (net (code "40") (name "Net-(D28-12)") (class "Default")
      (node (ref "D28") (pin "2") (pinfunction "12_2") (pintype "passive"))
      (node (ref "R87") (pin "2") (pinfunction "2_2") (pintype "passive"))
    )
    (net (code "41") (name "Net-(D29-10)") (class "Default")
      (node (ref "D29") (pin "3") (pinfunction "10_3") (pintype "passive"))
      (node (ref "R88") (pin "2") (pinfunction "2_2") (pintype "passive"))
    )
    (net (code "42") (name "Net-(D29-11)") (class "Default")
      (node (ref "D29") (pin "1") (pinfunction "11_1") (pintype "passive"))
      (node (ref "R90") (pin "1") (pinfunction "1_1") (pintype "passive"))
    )
    (net (code "43") (name "Net-(D29-12)") (class "Default")
      (node (ref "D29") (pin "2") (pinfunction "12_2") (pintype "passive"))
      (node (ref "R91") (pin "2") (pinfunction "2_2") (pintype "passive"))
    )
    (net (code "44") (name "Net-(D30-10)") (class "Default")
      (node (ref "D30") (pin "3") (pinfunction "10_3") (pintype "passive"))
      (node (ref "R89") (pin "2") (pinfunction "2_2") (pintype "passive"))
    )
    (net (code "45") (name "Net-(D30-11)") (class "Default")
      (node (ref "D30") (pin "1") (pinfunction "11_1") (pintype "passive"))
      (node (ref "R92") (pin "1") (pinfunction "1_1") (pintype "passive"))
    )
    (net (code "46") (name "Net-(D30-12)") (class "Default")
      (node (ref "D30") (pin "2") (pinfunction "12_2") (pintype "passive"))
      (node (ref "R93") (pin "2") (pinfunction "2_2") (pintype "passive"))
    )
    (net (code "47") (name "Net-(D31-10)") (class "Default")
      (node (ref "D31") (pin "3") (pinfunction "10_3") (pintype "passive"))
      (node (ref "R94") (pin "2") (pinfunction "2_2") (pintype "passive"))
    )
    (net (code "48") (name "Net-(D31-11)") (class "Default")
      (node (ref "D31") (pin "1") (pinfunction "11_1") (pintype "passive"))
      (node (ref "R96") (pin "1") (pinfunction "1_1") (pintype "passive"))
    )
    (net (code "49") (name "Net-(D31-12)") (class "Default")
      (node (ref "D31") (pin "2") (pinfunction "12_2") (pintype "passive"))
      (node (ref "R97") (pin "2") (pinfunction "2_2") (pintype "passive"))
    )
    (net (code "50") (name "Net-(D32-10)") (class "Default")
      (node (ref "D32") (pin "3") (pinfunction "10_3") (pintype "passive"))
      (node (ref "R95") (pin "2") (pinfunction "2_2") (pintype "passive"))
    )
    (net (code "51") (name "Net-(D32-11)") (class "Default")
      (node (ref "D32") (pin "1") (pinfunction "11_1") (pintype "passive"))
      (node (ref "R98") (pin "1") (pinfunction "1_1") (pintype "passive"))
    )
    (net (code "52") (name "Net-(D32-12)") (class "Default")
      (node (ref "D32") (pin "2") (pinfunction "12_2") (pintype "passive"))
      (node (ref "R99") (pin "2") (pinfunction "2_2") (pintype "passive"))
    )
  )
)
